# Large_Mosfet.net
KiCad netlist of a schematic drawn in EAGLE
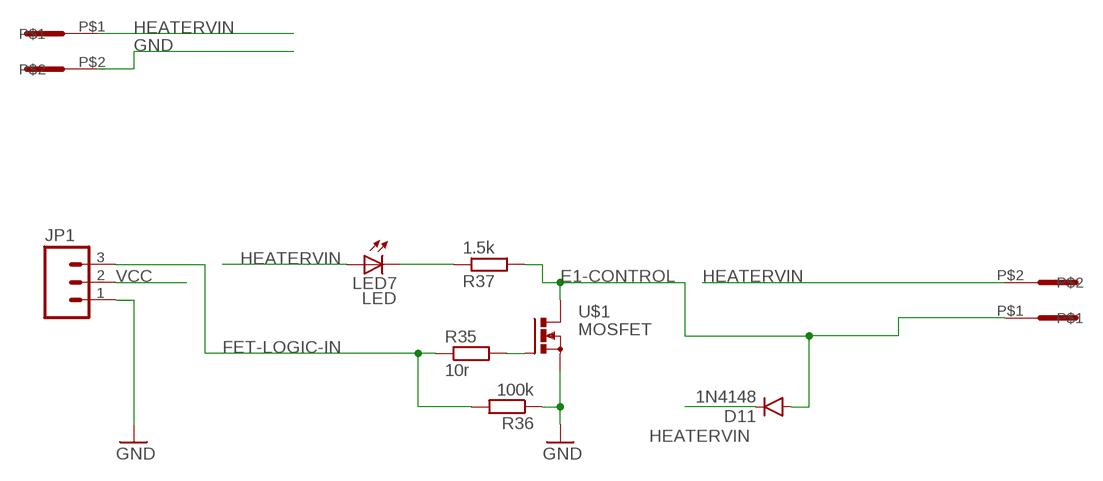
[diagram p0: schematic, sheet 1]

(export (version "E")
  (design (tool "Eeschema 10.0.6"))
  (components
    (comp (ref "D11")
      (value "1N4148")
      (footprint "eagle-import:SOD-323")
      (libsource (lib "eagle-import") (part "DIODEBAS16"))
    )
    (comp (ref "JP1")
      (value "M03LOCK")
      (footprint "eagle-import:1X03_LOCK")
      (libsource (lib "eagle-import") (part "M03LOCK"))
    )
    (comp (ref "LED7")
      (value "LED")
      (footprint "eagle-import:SML0603")
      (libsource (lib "eagle-import") (part "LEDSML0603"))
    )
    (comp (ref "R35")
      (value "10r")
      (footprint "eagle-import:R0603")
      (libsource (lib "eagle-import") (part "R-EU_R0603"))
    )
    (comp (ref "R36")
      (value "100k")
      (footprint "eagle-import:R0603")
      (libsource (lib "eagle-import") (part "R-EU_R0603"))
    )
    (comp (ref "R37")
      (value "1.5k")
      (footprint "eagle-import:R0603")
      (libsource (lib "eagle-import") (part "R-EU_R0603"))
    )
    (comp (ref "U$1")
      (value "MOSFET")
      (footprint "eagle-import:D2PACK")
      (libsource (lib "eagle-import") (part "N-POWER-MOSFETD2PAK-MOSFET"))
    )
    (comp (ref "U$2")
      (value "5MMCONN")
      (footprint "eagle-import:1715250000")
      (libsource (lib "eagle-import") (part "5MMCONN"))
    )
    (comp (ref "U$6")
      (value "5MMCONN")
      (footprint "eagle-import:1715250000")
      (libsource (lib "eagle-import") (part "5MMCONN"))
    )
  )
  (nets
    (net (code "1") (name "/E1-CONTROL") (class "Default")
      (node (ref "D11") (pin "A") (pinfunction "A_A") (pintype "passive"))
      (node (ref "R37") (pin "2") (pinfunction "2_2") (pintype "passive"))
      (node (ref "U$1") (pin "2") (pinfunction "D_2") (pintype "passive"))
      (node (ref "U$2") (pin "P$1") (pinfunction "P$1_P$1") (pintype "bidirectional"))
    )
    (net (code "2") (name "/FET-LOGIC-IN") (class "Default")
      (node (ref "JP1") (pin "3") (pinfunction "3_3") (pintype "passive"))
      (node (ref "R35") (pin "1") (pinfunction "1_1") (pintype "passive"))
      (node (ref "R36") (pin "2") (pinfunction "2_2") (pintype "passive"))
    )
    (net (code "3") (name "/HEATERVIN") (class "Default")
      (node (ref "D11") (pin "C") (pinfunction "C_C") (pintype "passive"))
      (node (ref "LED7") (pin "A") (pinfunction "A_A") (pintype "passive"))
      (node (ref "U$2") (pin "P$2") (pinfunction "P$2_P$2") (pintype "bidirectional"))
      (node (ref "U$6") (pin "P$1") (pinfunction "P$1_P$1") (pintype "bidirectional"))
    )
    (net (code "4") (name "/VCC") (class "Default")
      (node (ref "JP1") (pin "2") (pinfunction "2_2") (pintype "passive"))
    )
    (net (code "5") (name "GND") (class "Default")
      (node (ref "JP1") (pin "1") (pinfunction "1_1") (pintype "passive"))
      (node (ref "R36") (pin "1") (pinfunction "1_1") (pintype "passive"))
      (node (ref "U$1") (pin "3") (pinfunction "S_3") (pintype "passive"))
      (node (ref "U$6") (pin "P$2") (pinfunction "P$2_P$2") (pintype "bidirectional"))
    )
    (net (code "6") (name "Net-(LED7-PadC)") (class "Default")
      (node (ref "LED7") (pin "C") (pinfunction "C_C") (pintype "passive"))
      (node (ref "R37") (pin "1") (pinfunction "1_1") (pintype "passive"))
    )
    (net (code "7") (name "Net-(U$1-G)") (class "Default")
      (node (ref "R35") (pin "2") (pinfunction "2_2") (pintype "passive"))
      (node (ref "U$1") (pin "1") (pinfunction "G_1") (pintype "passive"))
    )
  )
)
